# CAN-MOT-SQIN.net
KiCad netlist of a schematic drawn in EAGLE
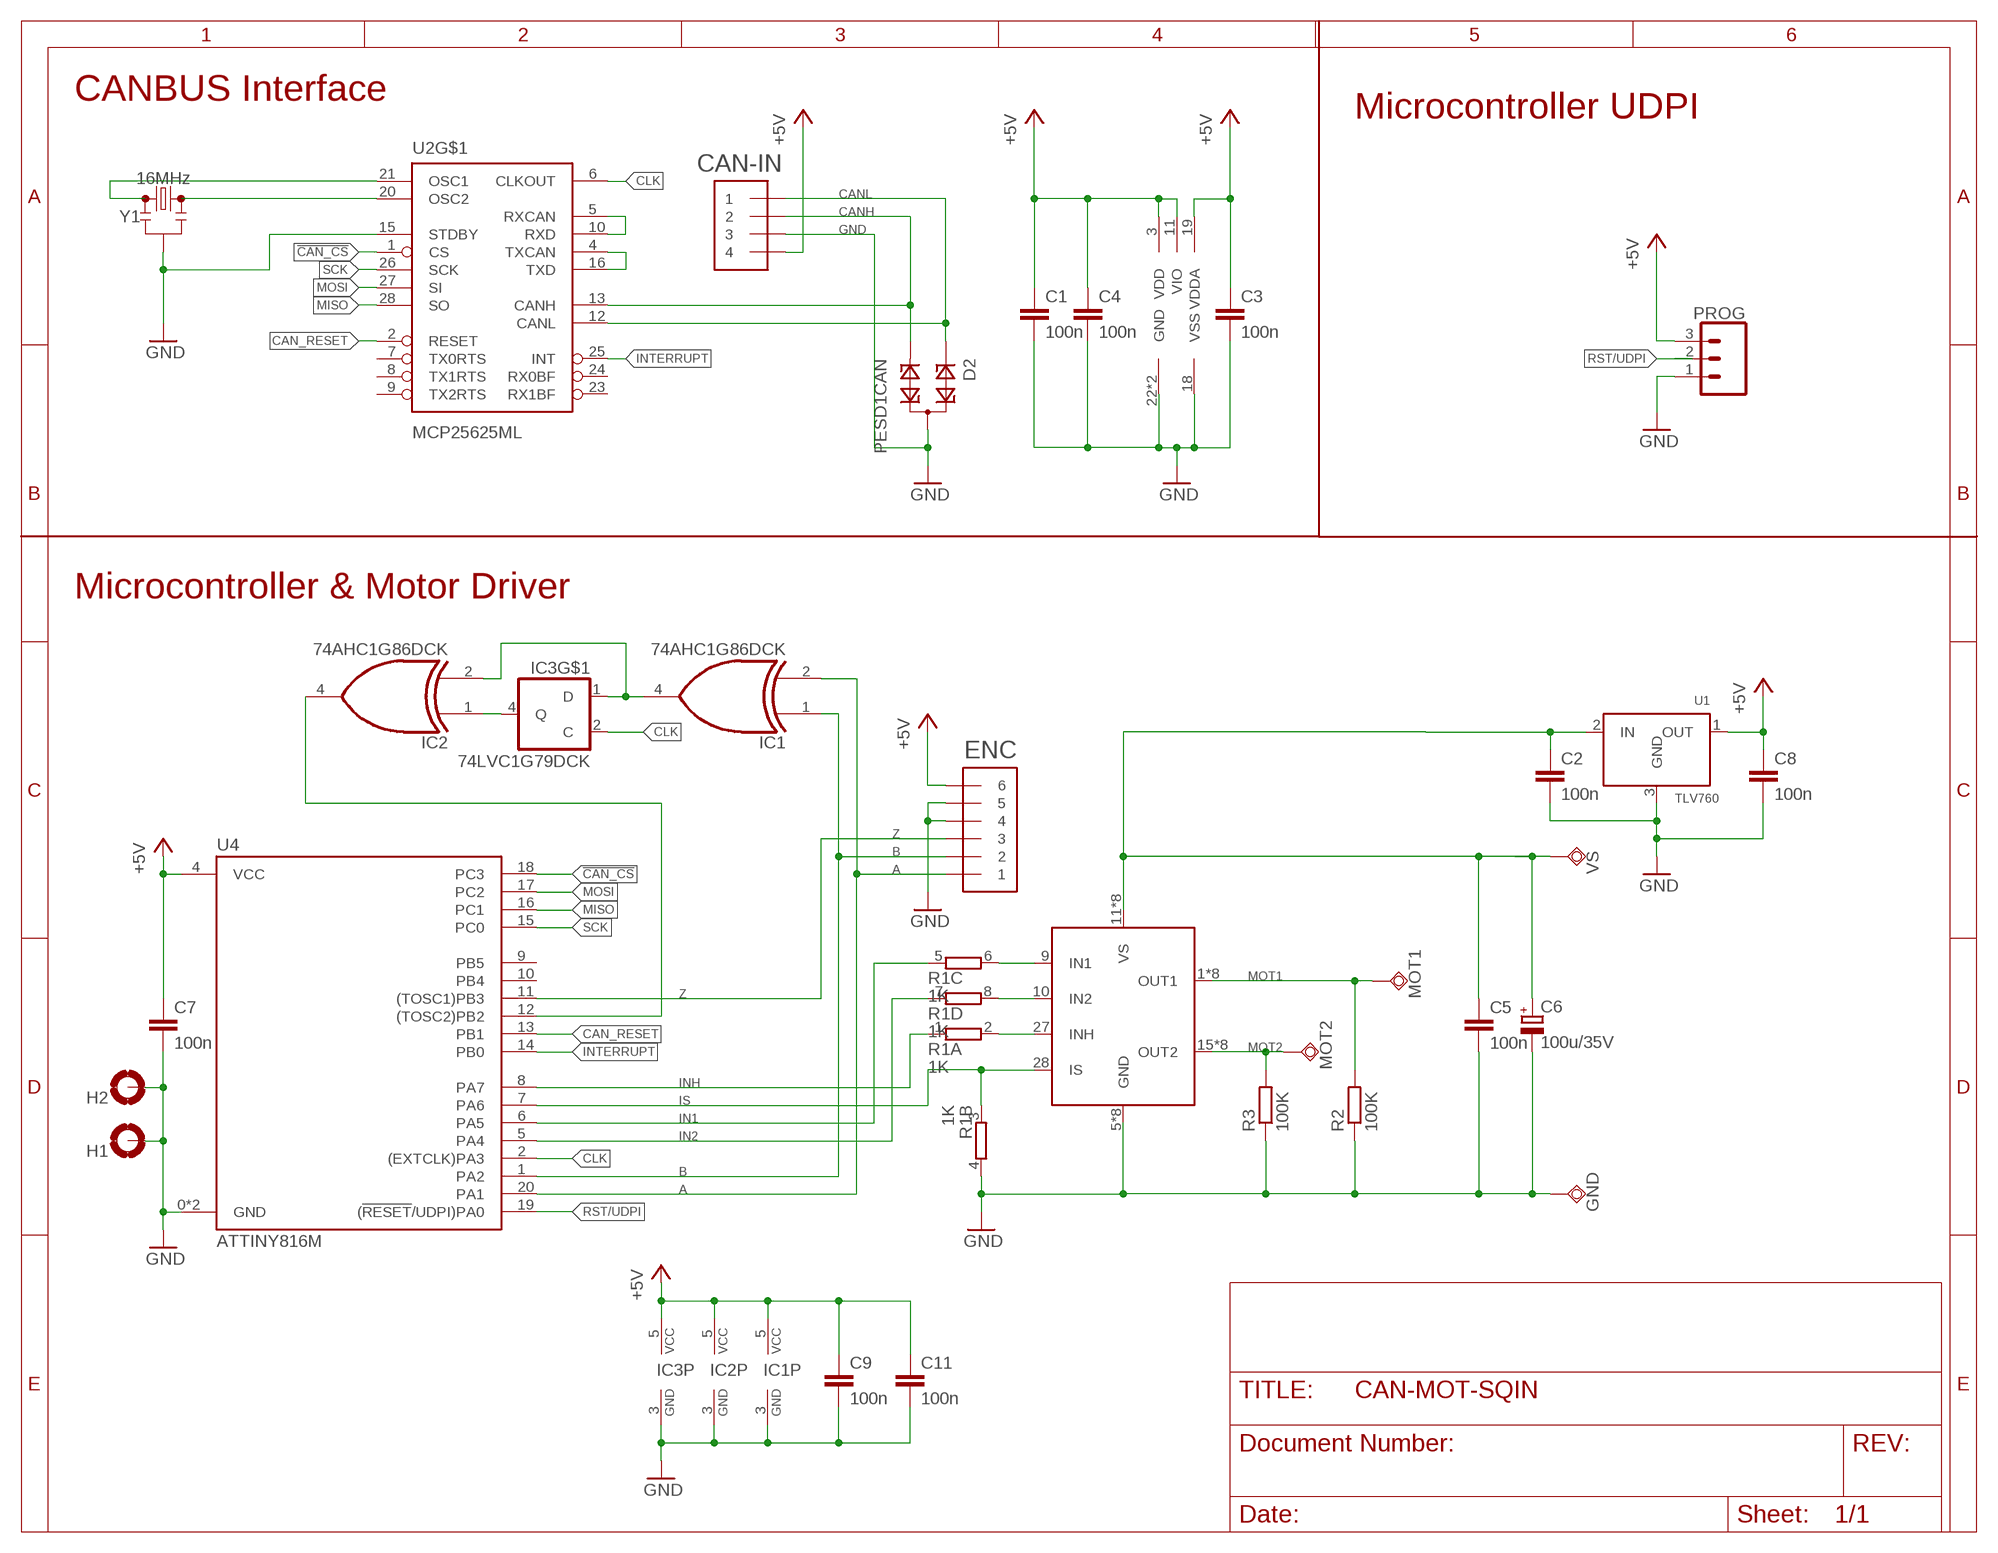
[diagram p0: schematic, sheet 1]

(export (version "E")
  (design (tool "Eeschema 10.0.6"))
  (components
    (comp (ref "C1")
      (value "100n")
      (footprint "eagle-import:C0603")
      (libsource (lib "eagle-import") (part "C-EUC0603"))
    )
    (comp (ref "C2")
      (value "100n")
      (footprint "eagle-import:C0603")
      (libsource (lib "eagle-import") (part "C-EUC0603"))
    )
    (comp (ref "C3")
      (value "100n")
      (footprint "eagle-import:C0603")
      (libsource (lib "eagle-import") (part "C-EUC0603"))
    )
    (comp (ref "C4")
      (value "100n")
      (footprint "eagle-import:C0603")
      (libsource (lib "eagle-import") (part "C-EUC0603"))
    )
    (comp (ref "C5")
      (value "100n")
      (footprint "eagle-import:C0603")
      (libsource (lib "eagle-import") (part "C-EUC0603"))
    )
    (comp (ref "C6")
      (value "100u/35V")
      (footprint "eagle-import:PANASONIC_D")
      (libsource (lib "eagle-import") (part "CPOL-EUD"))
    )
    (comp (ref "C7")
      (value "100n")
      (footprint "eagle-import:C0603")
      (libsource (lib "eagle-import") (part "C-EUC0603"))
    )
    (comp (ref "C8")
      (value "100n")
      (footprint "eagle-import:C0603")
      (libsource (lib "eagle-import") (part "C-EUC0603"))
    )
    (comp (ref "C9")
      (value "100n")
      (footprint "eagle-import:C0603")
      (libsource (lib "eagle-import") (part "C-EUC0603"))
    )
    (comp (ref "C11")
      (value "100n")
      (footprint "eagle-import:C0603")
      (libsource (lib "eagle-import") (part "C-EUC0603"))
    )
    (comp (ref "CAN-IN")
      (value "STRAWSON_EAGLE_LIB_JST_SH_4")
      (footprint "eagle-import:STRAWSON_EAGLE_LIB_JST_SH_4_SMD")
      (libsource (lib "eagle-import") (part "STRAWSON_EAGLE_LIB_JST_SH_4"))
    )
    (comp (ref "D2")
      (value "PESD1CAN")
      (footprint "eagle-import:SOT23")
      (libsource (lib "eagle-import") (part "PESD1CAN"))
    )
    (comp (ref "ENC")
      (value "STRAWSON_EAGLE_LIB_JST_SH_6")
      (footprint "eagle-import:STRAWSON_EAGLE_LIB_JST_SH_6")
      (libsource (lib "eagle-import") (part "STRAWSON_EAGLE_LIB_JST_SH_6"))
    )
    (comp (ref "GND")
      (value "TPSQTP20SQ")
      (footprint "eagle-import:TP20SQ")
      (libsource (lib "eagle-import") (part "TPSQTP20SQ"))
    )
    (comp (ref "H1")
      (value "MOUNT-PAD-ROUND2.8")
      (footprint "eagle-import:2,8-PAD")
      (libsource (lib "eagle-import") (part "MOUNT-PAD-ROUND2.8"))
    )
    (comp (ref "H2")
      (value "MOUNT-PAD-ROUND2.8")
      (footprint "eagle-import:2,8-PAD")
      (libsource (lib "eagle-import") (part "MOUNT-PAD-ROUND2.8"))
    )
    (comp (ref "IC1")
      (value "74AHC1G86DCK")
      (footprint "eagle-import:SC70-5")
      (libsource (lib "eagle-import") (part "741G86DCKAHC"))
    )
    (comp (ref "IC2")
      (value "74AHC1G86DCK")
      (footprint "eagle-import:SC70-5")
      (libsource (lib "eagle-import") (part "741G86DCKAHC"))
    )
    (comp (ref "IC3")
      (value "74LVC1G79DCK")
      (footprint "eagle-import:SC70-5")
      (libsource (lib "eagle-import") (part "741G79DCKLVC"))
    )
    (comp (ref "MOT1")
      (value "TPSQTP20SQ")
      (footprint "eagle-import:TP20SQ")
      (libsource (lib "eagle-import") (part "TPSQTP20SQ"))
    )
    (comp (ref "MOT2")
      (value "TPSQTP20SQ")
      (footprint "eagle-import:TP20SQ")
      (libsource (lib "eagle-import") (part "TPSQTP20SQ"))
    )
    (comp (ref "PROG")
      (value "CONN_03LOCK")
      (footprint "eagle-import:1X03_LOCK")
      (libsource (lib "eagle-import") (part "CONN_03LOCK"))
    )
    (comp (ref "R1")
      (value "1K")
      (footprint "eagle-import:CTS742C083-RES")
      (libsource (lib "eagle-import") (part "4R-NCTS742C083"))
    )
    (comp (ref "R2")
      (value "100K")
      (footprint "eagle-import:R0603")
      (libsource (lib "eagle-import") (part "R-EU_R0603"))
    )
    (comp (ref "R3")
      (value "100K")
      (footprint "eagle-import:R0603")
      (libsource (lib "eagle-import") (part "R-EU_R0603"))
    )
    (comp (ref "U1")
      (value "TLV760")
      (footprint "eagle-import:SOT23")
      (libsource (lib "eagle-import") (part "TLV760"))
    )
    (comp (ref "U2")
      (value "MCP25625ML")
      (footprint "eagle-import:QFN-28(6X6)")
      (libsource (lib "eagle-import") (part "MCP25625ML"))
    )
    (comp (ref "U3")
      (value "BTM7752G")
      (footprint "eagle-import:PG-DSO-36-29")
      (libsource (lib "eagle-import") (part "BTM7752G"))
    )
    (comp (ref "U4")
      (value "ATTINY816M")
      (footprint "eagle-import:QFN20")
      (libsource (lib "eagle-import") (part "ATTINY816M"))
    )
    (comp (ref "VS")
      (value "TPSQTP20SQ")
      (footprint "eagle-import:TP20SQ")
      (libsource (lib "eagle-import") (part "TPSQTP20SQ"))
    )
    (comp (ref "Y1")
      (value "16MHz")
      (footprint "eagle-import:RESONATOR-SMD-3.2X1.3")
      (fields (field (name "PARTNO") "PRQC16.00CR5010X000 "))
      (libsource (lib "eagle-import") (part "RESONATOR-16MHZSMD_3.2X1.3"))
    )
  )
  (nets
    (net (code "1") (name "+5V") (class "Default")
      (node (ref "C1") (pin "1") (pinfunction "1_1") (pintype "passive"))
      (node (ref "C11") (pin "1") (pinfunction "1_1") (pintype "passive"))
      (node (ref "C3") (pin "1") (pinfunction "1_1") (pintype "passive"))
      (node (ref "C4") (pin "1") (pinfunction "1_1") (pintype "passive"))
      (node (ref "C7") (pin "1") (pinfunction "1_1") (pintype "passive"))
      (node (ref "C8") (pin "1") (pinfunction "1_1") (pintype "passive"))
      (node (ref "C9") (pin "1") (pinfunction "1_1") (pintype "passive"))
      (node (ref "CAN-IN") (pin "4") (pinfunction "4_4") (pintype "bidirectional"))
      (node (ref "ENC") (pin "6") (pinfunction "6_6") (pintype "bidirectional"))
      (node (ref "IC1") (pin "5") (pinfunction "VCC_5") (pintype "power_in"))
      (node (ref "IC2") (pin "5") (pinfunction "VCC_5") (pintype "power_in"))
      (node (ref "IC3") (pin "5") (pinfunction "VCC_5") (pintype "power_in"))
      (node (ref "PROG") (pin "3") (pinfunction "3_3") (pintype "passive"))
      (node (ref "U1") (pin "1") (pinfunction "OUT_1") (pintype "bidirectional"))
      (node (ref "U2") (pin "11") (pinfunction "VIO_11") (pintype "bidirectional"))
      (node (ref "U2") (pin "19") (pinfunction "VDDA_19") (pintype "bidirectional"))
      (node (ref "U2") (pin "3") (pinfunction "VDD_3") (pintype "bidirectional"))
      (node (ref "U4") (pin "4") (pinfunction "VCC_4") (pintype "bidirectional"))
    )
    (net (code "2") (name "/A") (class "Default")
      (node (ref "ENC") (pin "1") (pinfunction "1_1") (pintype "bidirectional"))
      (node (ref "IC1") (pin "2") (pinfunction "I1_2") (pintype "input"))
      (node (ref "U4") (pin "20") (pinfunction "PA1_20") (pintype "bidirectional"))
    )
    (net (code "3") (name "/B") (class "Default")
      (node (ref "ENC") (pin "2") (pinfunction "2_2") (pintype "bidirectional"))
      (node (ref "IC1") (pin "1") (pinfunction "I0_1") (pintype "input"))
      (node (ref "U4") (pin "1") (pinfunction "PA2_1") (pintype "bidirectional"))
    )
    (net (code "4") (name "/CANH") (class "Default")
      (node (ref "CAN-IN") (pin "2") (pinfunction "2_2") (pintype "bidirectional"))
      (node (ref "D2") (pin "2") (pinfunction "2_2") (pintype "passive"))
      (node (ref "U2") (pin "13") (pinfunction "CANH_13") (pintype "output"))
    )
    (net (code "5") (name "/CANL") (class "Default")
      (node (ref "CAN-IN") (pin "1") (pinfunction "1_1") (pintype "bidirectional"))
      (node (ref "D2") (pin "1") (pinfunction "1_1") (pintype "passive"))
      (node (ref "U2") (pin "12") (pinfunction "CANL_12") (pintype "output"))
    )
    (net (code "6") (name "/IN1") (class "Default")
      (node (ref "R1") (pin "5") (pinfunction "1_5") (pintype "passive"))
      (node (ref "U4") (pin "6") (pinfunction "PA5_6") (pintype "bidirectional"))
    )
    (net (code "7") (name "/IN2") (class "Default")
      (node (ref "R1") (pin "7") (pinfunction "1_7") (pintype "passive"))
      (node (ref "U4") (pin "5") (pinfunction "PA4_5") (pintype "bidirectional"))
    )
    (net (code "8") (name "/INH") (class "Default")
      (node (ref "R1") (pin "1") (pinfunction "1_1") (pintype "passive"))
      (node (ref "U4") (pin "8") (pinfunction "PA7_8") (pintype "bidirectional"))
    )
    (net (code "9") (name "/IS") (class "Default")
      (node (ref "R1") (pin "3") (pinfunction "1_3") (pintype "passive"))
      (node (ref "U3") (pin "28") (pinfunction "IS_28") (pintype "bidirectional"))
      (node (ref "U4") (pin "7") (pinfunction "PA6_7") (pintype "bidirectional"))
    )
    (net (code "10") (name "/MOT1") (class "Default")
      (node (ref "MOT1") (pin "TP") (pinfunction "TP_TP") (pintype "input"))
      (node (ref "R2") (pin "2") (pinfunction "2_2") (pintype "passive"))
      (node (ref "U3") (pin "1") (pinfunction "OUT1_1") (pintype "bidirectional"))
      (node (ref "U3") (pin "2") (pinfunction "OUT1_2") (pintype "bidirectional"))
      (node (ref "U3") (pin "3") (pinfunction "OUT1_3") (pintype "bidirectional"))
      (node (ref "U3") (pin "33") (pinfunction "OUT1_33") (pintype "bidirectional"))
      (node (ref "U3") (pin "34") (pinfunction "OUT1_34") (pintype "bidirectional"))
      (node (ref "U3") (pin "35") (pinfunction "OUT1_35") (pintype "bidirectional"))
      (node (ref "U3") (pin "36") (pinfunction "OUT1_36") (pintype "bidirectional"))
      (node (ref "U3") (pin "4") (pinfunction "OUT1_4") (pintype "bidirectional"))
    )
    (net (code "11") (name "/MOT2") (class "Default")
      (node (ref "MOT2") (pin "TP") (pinfunction "TP_TP") (pintype "input"))
      (node (ref "R3") (pin "2") (pinfunction "2_2") (pintype "passive"))
      (node (ref "U3") (pin "15") (pinfunction "OUT2_15") (pintype "bidirectional"))
      (node (ref "U3") (pin "16") (pinfunction "OUT2_16") (pintype "bidirectional"))
      (node (ref "U3") (pin "17") (pinfunction "OUT2_17") (pintype "bidirectional"))
      (node (ref "U3") (pin "18") (pinfunction "OUT2_18") (pintype "bidirectional"))
      (node (ref "U3") (pin "19") (pinfunction "OUT2_19") (pintype "bidirectional"))
      (node (ref "U3") (pin "20") (pinfunction "OUT2_20") (pintype "bidirectional"))
      (node (ref "U3") (pin "21") (pinfunction "OUT2_21") (pintype "bidirectional"))
      (node (ref "U3") (pin "22") (pinfunction "OUT2_22") (pintype "bidirectional"))
    )
    (net (code "12") (name "/Z") (class "Default")
      (node (ref "ENC") (pin "3") (pinfunction "3_3") (pintype "bidirectional"))
      (node (ref "U4") (pin "11") (pinfunction "(TOSC1)PB3_11") (pintype "bidirectional"))
    )
    (net (code "13") (name "/~{CAN_CS}") (class "Default")
      (node (ref "U2") (pin "1") (pinfunction "CS_1") (pintype "input"))
      (node (ref "U4") (pin "18") (pinfunction "PC3_18") (pintype "bidirectional"))
    )
    (net (code "14") (name "CAN_RESET") (class "Default")
      (node (ref "U2") (pin "2") (pinfunction "RESET_2") (pintype "input"))
      (node (ref "U4") (pin "13") (pinfunction "PB1_13") (pintype "bidirectional"))
    )
    (net (code "15") (name "CLK") (class "Default")
      (node (ref "IC3") (pin "2") (pinfunction "C_2") (pintype "input"))
      (node (ref "U2") (pin "6") (pinfunction "CLKOUT_6") (pintype "output"))
      (node (ref "U4") (pin "2") (pinfunction "(EXTCLK)PA3_2") (pintype "bidirectional"))
    )
    (net (code "16") (name "GND") (class "Default")
      (node (ref "C1") (pin "2") (pinfunction "2_2") (pintype "passive"))
      (node (ref "C11") (pin "2") (pinfunction "2_2") (pintype "passive"))
      (node (ref "C2") (pin "2") (pinfunction "2_2") (pintype "passive"))
      (node (ref "C3") (pin "2") (pinfunction "2_2") (pintype "passive"))
      (node (ref "C4") (pin "2") (pinfunction "2_2") (pintype "passive"))
      (node (ref "C5") (pin "2") (pinfunction "2_2") (pintype "passive"))
      (node (ref "C6") (pin "-") (pinfunction "-_-") (pintype "passive"))
      (node (ref "C7") (pin "2") (pinfunction "2_2") (pintype "passive"))
      (node (ref "C8") (pin "2") (pinfunction "2_2") (pintype "passive"))
      (node (ref "C9") (pin "2") (pinfunction "2_2") (pintype "passive"))
      (node (ref "CAN-IN") (pin "3") (pinfunction "3_3") (pintype "bidirectional"))
      (node (ref "D2") (pin "3") (pinfunction "3_3") (pintype "passive"))
      (node (ref "ENC") (pin "4") (pinfunction "4_4") (pintype "bidirectional"))
      (node (ref "ENC") (pin "5") (pinfunction "5_5") (pintype "bidirectional"))
      (node (ref "GND") (pin "TP") (pinfunction "TP_TP") (pintype "input"))
      (node (ref "H1") (pin "B2,8") (pinfunction "MOUNT_B2,8") (pintype "passive"))
      (node (ref "H2") (pin "B2,8") (pinfunction "MOUNT_B2,8") (pintype "passive"))
      (node (ref "IC1") (pin "3") (pinfunction "GND_3") (pintype "power_in"))
      (node (ref "IC2") (pin "3") (pinfunction "GND_3") (pintype "power_in"))
      (node (ref "IC3") (pin "3") (pinfunction "GND_3") (pintype "power_in"))
      (node (ref "PROG") (pin "1") (pinfunction "1_1") (pintype "passive"))
      (node (ref "R1") (pin "4") (pinfunction "2_4") (pintype "passive"))
      (node (ref "R2") (pin "1") (pinfunction "1_1") (pintype "passive"))
      (node (ref "R3") (pin "1") (pinfunction "1_1") (pintype "passive"))
      (node (ref "U1") (pin "3") (pinfunction "GND_3") (pintype "bidirectional"))
      (node (ref "U2") (pin "15") (pinfunction "STDBY_15") (pintype "output"))
      (node (ref "U2") (pin "18") (pinfunction "VSS_18") (pintype "bidirectional"))
      (node (ref "U2") (pin "22") (pinfunction "GND_22") (pintype "bidirectional"))
      (node (ref "U2") (pin "EP") (pinfunction "GND_EP") (pintype "bidirectional"))
      (node (ref "U3") (pin "23") (pinfunction "GND_23") (pintype "bidirectional"))
      (node (ref "U3") (pin "24") (pinfunction "GND_24") (pintype "bidirectional"))
      (node (ref "U3") (pin "25") (pinfunction "GND_25") (pintype "bidirectional"))
      (node (ref "U3") (pin "26") (pinfunction "GND_26") (pintype "bidirectional"))
      (node (ref "U3") (pin "5") (pinfunction "GND_5") (pintype "bidirectional"))
      (node (ref "U3") (pin "6") (pinfunction "GND_6") (pintype "bidirectional"))
      (node (ref "U3") (pin "7") (pinfunction "GND_7") (pintype "bidirectional"))
      (node (ref "U3") (pin "8") (pinfunction "GND_8") (pintype "bidirectional"))
      (node (ref "U4") (pin "0") (pinfunction "GND_0") (pintype "bidirectional"))
      (node (ref "U4") (pin "3") (pinfunction "GND_3") (pintype "bidirectional"))
      (node (ref "Y1") (pin "2") (pinfunction "2_2") (pintype "passive"))
    )
    (net (code "17") (name "INTERRUPT") (class "Default")
      (node (ref "U2") (pin "25") (pinfunction "INT_25") (pintype "output"))
      (node (ref "U4") (pin "14") (pinfunction "PB0_14") (pintype "bidirectional"))
    )
    (net (code "18") (name "MISO") (class "Default")
      (node (ref "U2") (pin "28") (pinfunction "SO_28") (pintype "output"))
      (node (ref "U4") (pin "16") (pinfunction "PC1_16") (pintype "bidirectional"))
    )
    (net (code "19") (name "MOSI") (class "Default")
      (node (ref "U2") (pin "27") (pinfunction "SI_27") (pintype "input"))
      (node (ref "U4") (pin "17") (pinfunction "PC2_17") (pintype "bidirectional"))
    )
    (net (code "20") (name "Net-(IC1A-O)") (class "Default")
      (node (ref "IC1") (pin "4") (pinfunction "O_4") (pintype "output"))
      (node (ref "IC2") (pin "2") (pinfunction "I1_2") (pintype "input"))
      (node (ref "IC3") (pin "1") (pinfunction "D_1") (pintype "input"))
    )
    (net (code "21") (name "Net-(IC2A-I0)") (class "Default")
      (node (ref "IC2") (pin "1") (pinfunction "I0_1") (pintype "input"))
      (node (ref "IC3") (pin "4") (pinfunction "Q_4") (pintype "output"))
    )
    (net (code "22") (name "Net-(IC2A-O)") (class "Default")
      (node (ref "IC2") (pin "4") (pinfunction "O_4") (pintype "output"))
      (node (ref "U4") (pin "12") (pinfunction "(TOSC2)PB2_12") (pintype "bidirectional"))
    )
    (net (code "23") (name "Net-(R1C-2)") (class "Default")
      (node (ref "R1") (pin "6") (pinfunction "2_6") (pintype "passive"))
      (node (ref "U3") (pin "9") (pinfunction "IN1_9") (pintype "bidirectional"))
    )
    (net (code "24") (name "Net-(R1D-2)") (class "Default")
      (node (ref "R1") (pin "8") (pinfunction "2_8") (pintype "passive"))
      (node (ref "U3") (pin "10") (pinfunction "IN2_10") (pintype "bidirectional"))
    )
    (net (code "25") (name "Net-(U1-IN)") (class "Default")
      (node (ref "C2") (pin "1") (pinfunction "1_1") (pintype "passive"))
      (node (ref "C5") (pin "1") (pinfunction "1_1") (pintype "passive"))
      (node (ref "C6") (pin "+") (pinfunction "+_+") (pintype "passive"))
      (node (ref "U1") (pin "2") (pinfunction "IN_2") (pintype "bidirectional"))
      (node (ref "U3") (pin "11") (pinfunction "VS_11") (pintype "bidirectional"))
      (node (ref "U3") (pin "12") (pinfunction "VS_12") (pintype "bidirectional"))
      (node (ref "U3") (pin "13") (pinfunction "VS_13") (pintype "bidirectional"))
      (node (ref "U3") (pin "14") (pinfunction "VS_14") (pintype "bidirectional"))
      (node (ref "U3") (pin "29") (pinfunction "VS_29") (pintype "bidirectional"))
      (node (ref "U3") (pin "30") (pinfunction "VS_30") (pintype "bidirectional"))
      (node (ref "U3") (pin "31") (pinfunction "VS_31") (pintype "bidirectional"))
      (node (ref "U3") (pin "32") (pinfunction "VS_32") (pintype "bidirectional"))
      (node (ref "VS") (pin "TP") (pinfunction "TP_TP") (pintype "input"))
    )
    (net (code "26") (name "Net-(U2A-OSC1)") (class "Default")
      (node (ref "U2") (pin "21") (pinfunction "OSC1_21") (pintype "input"))
      (node (ref "Y1") (pin "1") (pinfunction "1_1") (pintype "passive"))
    )
    (net (code "27") (name "Net-(U2A-OSC2)") (class "Default")
      (node (ref "U2") (pin "20") (pinfunction "OSC2_20") (pintype "output"))
      (node (ref "Y1") (pin "3") (pinfunction "3_3") (pintype "passive"))
    )
    (net (code "28") (name "Net-(U2A-RXCAN)") (class "Default")
      (node (ref "U2") (pin "10") (pinfunction "RXD_10") (pintype "input"))
      (node (ref "U2") (pin "5") (pinfunction "RXCAN_5") (pintype "input"))
    )
    (net (code "29") (name "Net-(U2A-TXCAN)") (class "Default")
      (node (ref "U2") (pin "16") (pinfunction "TXD_16") (pintype "output"))
      (node (ref "U2") (pin "4") (pinfunction "TXCAN_4") (pintype "output"))
    )
    (net (code "30") (name "Net-(U3-INH)") (class "Default")
      (node (ref "R1") (pin "2") (pinfunction "2_2") (pintype "passive"))
      (node (ref "U3") (pin "27") (pinfunction "INH_27") (pintype "bidirectional"))
    )
    (net (code "31") (name "RST{slash}UDPI") (class "Default")
      (node (ref "PROG") (pin "2") (pinfunction "2_2") (pintype "passive"))
      (node (ref "U4") (pin "19") (pinfunction "(~{RESET}/UDPI)PA0_19") (pintype "bidirectional"))
    )
    (net (code "32") (name "SCK") (class "Default")
      (node (ref "U2") (pin "26") (pinfunction "SCK_26") (pintype "input"))
      (node (ref "U4") (pin "15") (pinfunction "PC0_15") (pintype "bidirectional"))
    )
    (net (code "33") (name "unconnected-(U2A-RX0BF-Pad24)") (class "Default")
      (node (ref "U2") (pin "24") (pinfunction "RX0BF_24") (pintype "output"))
    )
    (net (code "34") (name "unconnected-(U2A-RX1BF-Pad23)") (class "Default")
      (node (ref "U2") (pin "23") (pinfunction "RX1BF_23") (pintype "output"))
    )
    (net (code "35") (name "unconnected-(U2A-TX0RTS-Pad7)") (class "Default")
      (node (ref "U2") (pin "7") (pinfunction "TX0RTS_7") (pintype "input"))
    )
    (net (code "36") (name "unconnected-(U2A-TX1RTS-Pad8)") (class "Default")
      (node (ref "U2") (pin "8") (pinfunction "TX1RTS_8") (pintype "input"))
    )
    (net (code "37") (name "unconnected-(U2A-TX2RTS-Pad9)") (class "Default")
      (node (ref "U2") (pin "9") (pinfunction "TX2RTS_9") (pintype "input"))
    )
    (net (code "38") (name "unconnected-(U4-PB4-Pad10)") (class "Default")
      (node (ref "U4") (pin "10") (pinfunction "PB4_10") (pintype "bidirectional"))
    )
    (net (code "39") (name "unconnected-(U4-PB5-Pad9)") (class "Default")
      (node (ref "U4") (pin "9") (pinfunction "PB5_9") (pintype "bidirectional"))
    )
  )
)
